# cooling_system.net
KiCad netlist of a schematic drawn in EAGLE
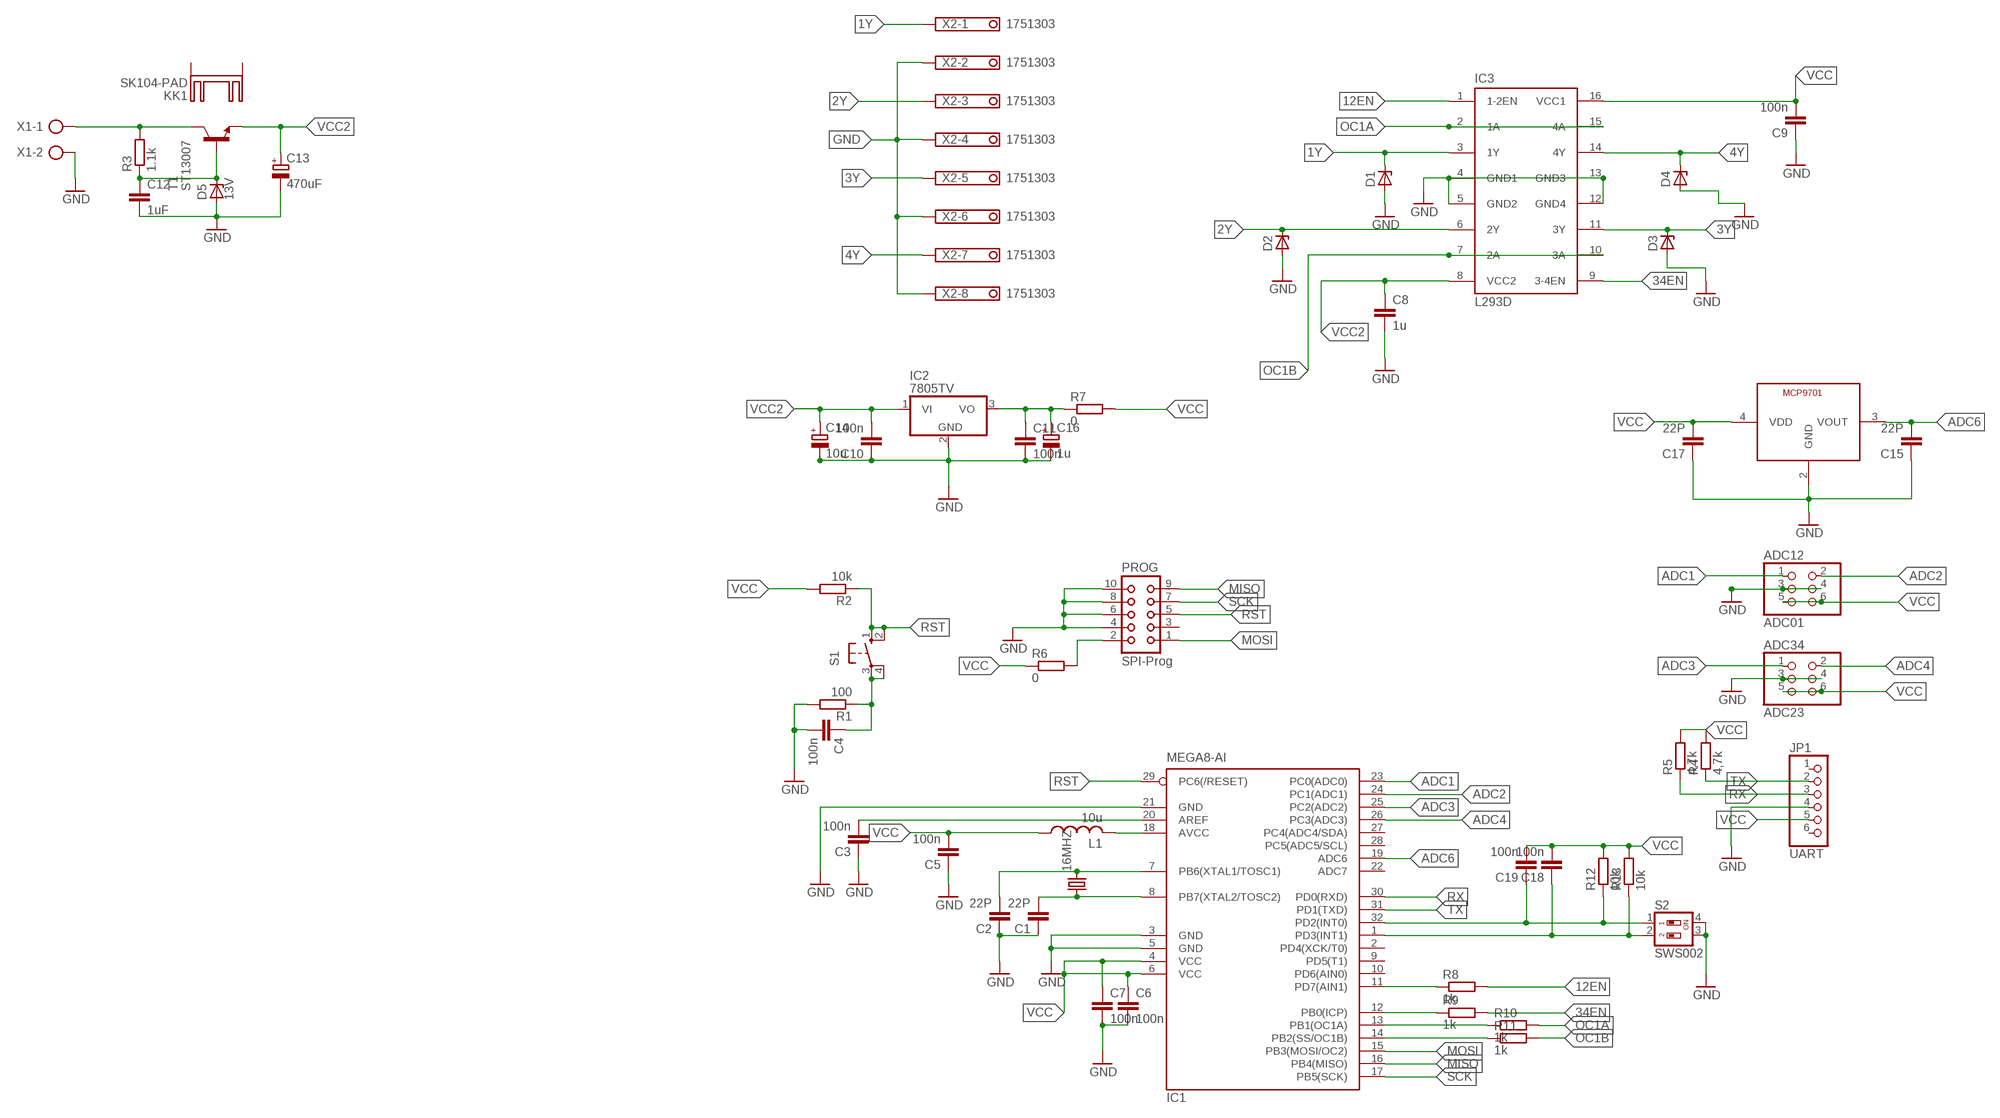
[diagram p0: schematic, sheet 1]

(export (version "E")
  (design (tool "Eeschema 10.0.6"))
  (components
    (comp (ref "16MHZ")
      (value "CRYSTALHC18U-V")
      (footprint "eagle-import:HC18U-V")
      (libsource (lib "eagle-import") (part "CRYSTALHC18U-V"))
    )
    (comp (ref "ADC12")
      (value "ADC01")
      (footprint "eagle-import:2X03")
      (libsource (lib "eagle-import") (part "PINHD-2X3"))
    )
    (comp (ref "ADC34")
      (value "ADC23")
      (footprint "eagle-import:2X03")
      (libsource (lib "eagle-import") (part "PINHD-2X3"))
    )
    (comp (ref "C1")
      (value "22P")
      (footprint "eagle-import:C0805K")
      (libsource (lib "eagle-import") (part "C-EUC0805K"))
    )
    (comp (ref "C2")
      (value "22P")
      (footprint "eagle-import:C0805K")
      (libsource (lib "eagle-import") (part "C-EUC0805K"))
    )
    (comp (ref "C3")
      (value "100n")
      (footprint "eagle-import:C0805K")
      (libsource (lib "eagle-import") (part "C-EUC0805K"))
    )
    (comp (ref "C4")
      (value "100n")
      (footprint "eagle-import:C0805K")
      (libsource (lib "eagle-import") (part "C-EUC0805K"))
    )
    (comp (ref "C5")
      (value "100n")
      (footprint "eagle-import:C0805K")
      (libsource (lib "eagle-import") (part "C-EUC0805K"))
    )
    (comp (ref "C6")
      (value "100n")
      (footprint "eagle-import:C0805K")
      (libsource (lib "eagle-import") (part "C-EUC0805K"))
    )
    (comp (ref "C7")
      (value "100n")
      (footprint "eagle-import:C0805K")
      (libsource (lib "eagle-import") (part "C-EUC0805K"))
    )
    (comp (ref "C8")
      (value "1u")
      (footprint "eagle-import:C0805K")
      (libsource (lib "eagle-import") (part "C-EUC0805K"))
    )
    (comp (ref "C9")
      (value "100n")
      (footprint "eagle-import:C0805K")
      (libsource (lib "eagle-import") (part "C-EUC0805K"))
    )
    (comp (ref "C10")
      (value "100n")
      (footprint "eagle-import:C0805K")
      (libsource (lib "eagle-import") (part "C-EUC0805K"))
    )
    (comp (ref "C11")
      (value "100n")
      (footprint "eagle-import:C0805K")
      (libsource (lib "eagle-import") (part "C-EUC0805K"))
    )
    (comp (ref "C12")
      (value "1uF")
      (footprint "eagle-import:C0805K")
      (libsource (lib "eagle-import") (part "C-EUC0805K"))
    )
    (comp (ref "C13")
      (value "470uF")
      (footprint "eagle-import:E5-10,5")
      (libsource (lib "eagle-import") (part "CPOL-EUE5-10.5"))
    )
    (comp (ref "C14")
      (value "10u")
      (footprint "eagle-import:153CLV-0505")
      (libsource (lib "eagle-import") (part "CPOL-EU153CLV-0505"))
    )
    (comp (ref "C15")
      (value "22P")
      (footprint "eagle-import:C0805K")
      (libsource (lib "eagle-import") (part "C-EUC0805K"))
    )
    (comp (ref "C16")
      (value "1u")
      (footprint "eagle-import:153CLV-0405")
      (libsource (lib "eagle-import") (part "CPOL-EU153CLV-0405"))
    )
    (comp (ref "C17")
      (value "22P")
      (footprint "eagle-import:C0805K")
      (libsource (lib "eagle-import") (part "C-EUC0805K"))
    )
    (comp (ref "C18")
      (value "100n")
      (footprint "eagle-import:C0805K")
      (libsource (lib "eagle-import") (part "C-EUC0805K"))
    )
    (comp (ref "C19")
      (value "100n")
      (footprint "eagle-import:C0805K")
      (libsource (lib "eagle-import") (part "C-EUC0805K"))
    )
    (comp (ref "D1")
      (value "ZENER-DIODEDO35Z10")
      (footprint "eagle-import:DO35Z10")
      (libsource (lib "eagle-import") (part "ZENER-DIODEDO35Z10"))
    )
    (comp (ref "D2")
      (value "ZENER-DIODEDO35Z10")
      (footprint "eagle-import:DO35Z10")
      (libsource (lib "eagle-import") (part "ZENER-DIODEDO35Z10"))
    )
    (comp (ref "D3")
      (value "ZENER-DIODEDO35Z10")
      (footprint "eagle-import:DO35Z10")
      (libsource (lib "eagle-import") (part "ZENER-DIODEDO35Z10"))
    )
    (comp (ref "D4")
      (value "ZENER-DIODEDO35Z10")
      (footprint "eagle-import:DO35Z10")
      (libsource (lib "eagle-import") (part "ZENER-DIODEDO35Z10"))
    )
    (comp (ref "D5")
      (value "13V")
      (footprint "eagle-import:SOT23")
      (libsource (lib "eagle-import") (part "ZENER-DIODESOT23"))
    )
    (comp (ref "IC1")
      (value "MEGA8-AI")
      (footprint "eagle-import:TQFP32-08")
      (fields (field (name "MPN") "ATMEGA8-16AU"))
      (libsource (lib "eagle-import") (part "MEGA8-AI"))
    )
    (comp (ref "IC2")
      (value "7805TV")
      (footprint "eagle-import:TO220V")
      (libsource (lib "eagle-import") (part "78TV05"))
    )
    (comp (ref "IC3")
      (value "L293D")
      (footprint "eagle-import:DIL16")
      (libsource (lib "eagle-import") (part "L293D"))
    )
    (comp (ref "JP1")
      (value "UART")
      (footprint "eagle-import:1X06")
      (libsource (lib "eagle-import") (part "PINHD-1X6"))
    )
    (comp (ref "KK1")
      (value "SK104-PAD")
      (footprint "eagle-import:SK104-PAD")
      (libsource (lib "eagle-import") (part "SK104-PAD"))
    )
    (comp (ref "L1")
      (value "10u")
      (footprint "eagle-import:0207_10")
      (libsource (lib "eagle-import") (part "L-US0207/10"))
    )
    (comp (ref "PROG")
      (value "SPI-Prog")
      (footprint "eagle-import:CON10")
      (libsource (lib "eagle-import") (part "CON10"))
    )
    (comp (ref "R1")
      (value "100")
      (footprint "eagle-import:0207_10")
      (libsource (lib "eagle-import") (part "R-EU_0207/10"))
    )
    (comp (ref "R2")
      (value "10k")
      (footprint "eagle-import:0207_10")
      (libsource (lib "eagle-import") (part "R-EU_0207/10"))
    )
    (comp (ref "R3")
      (value "1.1k")
      (footprint "eagle-import:R0805")
      (libsource (lib "eagle-import") (part "R-EU_R0805"))
    )
    (comp (ref "R4")
      (value "4,7k")
      (footprint "eagle-import:R0805")
      (libsource (lib "eagle-import") (part "R-EU_R0805"))
    )
    (comp (ref "R5")
      (value "4,7k")
      (footprint "eagle-import:R0805")
      (libsource (lib "eagle-import") (part "R-EU_R0805"))
    )
    (comp (ref "R6")
      (value "0")
      (footprint "eagle-import:R0805")
      (libsource (lib "eagle-import") (part "R-EU_R0805"))
    )
    (comp (ref "R7")
      (value "0")
      (footprint "eagle-import:R0805")
      (libsource (lib "eagle-import") (part "R-EU_R0805"))
    )
    (comp (ref "R8")
      (value "1k")
      (footprint "eagle-import:R0805")
      (libsource (lib "eagle-import") (part "R-EU_R0805"))
    )
    (comp (ref "R9")
      (value "1k")
      (footprint "eagle-import:R0805")
      (libsource (lib "eagle-import") (part "R-EU_R0805"))
    )
    (comp (ref "R10")
      (value "1k")
      (footprint "eagle-import:R0805")
      (libsource (lib "eagle-import") (part "R-EU_R0805"))
    )
    (comp (ref "R11")
      (value "1k")
      (footprint "eagle-import:R0805")
      (libsource (lib "eagle-import") (part "R-EU_R0805"))
    )
    (comp (ref "R12")
      (value "10k")
      (footprint "eagle-import:R0805")
      (libsource (lib "eagle-import") (part "R-EU_R0805"))
    )
    (comp (ref "R13")
      (value "10k")
      (footprint "eagle-import:R0805")
      (libsource (lib "eagle-import") (part "R-EU_R0805"))
    )
    (comp (ref "S1")
      (value "10-XX")
      (footprint "eagle-import:B3F-10XX")
      (fields (field (name "MPN") "B3F-1000"))
      (libsource (lib "eagle-import") (part "10-XX"))
    )
    (comp (ref "S2")
      (value "SWS002")
      (footprint "eagle-import:SMS-002")
      (libsource (lib "eagle-import") (part "SWS002"))
    )
    (comp (ref "T1")
      (value "ST13007")
      (footprint "eagle-import:TO220AV")
      (libsource (lib "eagle-import") (part "2SC2509V"))
    )
    (comp (ref "U$2")
      (value "MCP9701")
      (footprint "eagle-import:SC70-5L")
      (libsource (lib "eagle-import") (part "MCP9701"))
    )
    (comp (ref "X1")
      (value "AK300/2")
      (footprint "eagle-import:AK300_2")
      (libsource (lib "eagle-import") (part "AK300/2"))
    )
    (comp (ref "X2")
      (value "1751303")
      (footprint "eagle-import:1751303")
      (libsource (lib "eagle-import") (part "1751303"))
    )
  )
  (nets
    (net (code "1") (name "1Y") (class "Default")
      (node (ref "D1") (pin "C") (pinfunction "C_C") (pintype "passive"))
      (node (ref "IC3") (pin "3") (pinfunction "1Y_3") (pintype "output"))
      (node (ref "X2") (pin "1") (pinfunction "K_1") (pintype "passive"))
    )
    (net (code "2") (name "2Y") (class "Default")
      (node (ref "D2") (pin "C") (pinfunction "C_C") (pintype "passive"))
      (node (ref "IC3") (pin "6") (pinfunction "2Y_6") (pintype "output"))
      (node (ref "X2") (pin "3") (pinfunction "K_3") (pintype "passive"))
    )
    (net (code "3") (name "3Y") (class "Default")
      (node (ref "D3") (pin "C") (pinfunction "C_C") (pintype "passive"))
      (node (ref "IC3") (pin "11") (pinfunction "3Y_11") (pintype "output"))
      (node (ref "X2") (pin "5") (pinfunction "K_5") (pintype "passive"))
    )
    (net (code "4") (name "4Y") (class "Default")
      (node (ref "D4") (pin "C") (pinfunction "C_C") (pintype "passive"))
      (node (ref "IC3") (pin "14") (pinfunction "4Y_14") (pintype "output"))
      (node (ref "X2") (pin "7") (pinfunction "K_7") (pintype "passive"))
    )
    (net (code "5") (name "12EN") (class "Default")
      (node (ref "IC3") (pin "1") (pinfunction "1-2EN_1") (pintype "input"))
      (node (ref "R8") (pin "2") (pinfunction "2_2") (pintype "passive"))
    )
    (net (code "6") (name "34EN") (class "Default")
      (node (ref "IC3") (pin "9") (pinfunction "3-4EN_9") (pintype "input"))
      (node (ref "R9") (pin "2") (pinfunction "2_2") (pintype "passive"))
    )
    (net (code "7") (name "ADC1") (class "Default")
      (node (ref "ADC12") (pin "1") (pinfunction "1_1") (pintype "passive"))
      (node (ref "IC1") (pin "23") (pinfunction "PC0(ADC0)_23") (pintype "bidirectional"))
    )
    (net (code "8") (name "ADC2") (class "Default")
      (node (ref "ADC12") (pin "2") (pinfunction "2_2") (pintype "passive"))
      (node (ref "IC1") (pin "24") (pinfunction "PC1(ADC1)_24") (pintype "bidirectional"))
    )
    (net (code "9") (name "ADC3") (class "Default")
      (node (ref "ADC34") (pin "1") (pinfunction "1_1") (pintype "passive"))
      (node (ref "IC1") (pin "25") (pinfunction "PC2(ADC2)_25") (pintype "bidirectional"))
    )
    (net (code "10") (name "ADC4") (class "Default")
      (node (ref "ADC34") (pin "2") (pinfunction "2_2") (pintype "passive"))
      (node (ref "IC1") (pin "26") (pinfunction "PC3(ADC3)_26") (pintype "bidirectional"))
    )
    (net (code "11") (name "ADC6") (class "Default")
      (node (ref "C15") (pin "2") (pinfunction "2_2") (pintype "passive"))
      (node (ref "IC1") (pin "19") (pinfunction "ADC6_19") (pintype "bidirectional"))
      (node (ref "U$2") (pin "3") (pinfunction "VOUT_3") (pintype "bidirectional"))
    )
    (net (code "12") (name "GND") (class "Default")
      (node (ref "ADC12") (pin "3") (pinfunction "3_3") (pintype "passive"))
      (node (ref "ADC12") (pin "4") (pinfunction "4_4") (pintype "passive"))
      (node (ref "ADC34") (pin "3") (pinfunction "3_3") (pintype "passive"))
      (node (ref "ADC34") (pin "4") (pinfunction "4_4") (pintype "passive"))
      (node (ref "C1") (pin "1") (pinfunction "1_1") (pintype "passive"))
      (node (ref "C10") (pin "1") (pinfunction "1_1") (pintype "passive"))
      (node (ref "C11") (pin "2") (pinfunction "2_2") (pintype "passive"))
      (node (ref "C12") (pin "2") (pinfunction "2_2") (pintype "passive"))
      (node (ref "C13") (pin "-") (pinfunction "-_-") (pintype "passive"))
      (node (ref "C14") (pin "-") (pinfunction "-_-") (pintype "passive"))
      (node (ref "C15") (pin "1") (pinfunction "1_1") (pintype "passive"))
      (node (ref "C16") (pin "-") (pinfunction "-_-") (pintype "passive"))
      (node (ref "C17") (pin "1") (pinfunction "1_1") (pintype "passive"))
      (node (ref "C2") (pin "1") (pinfunction "1_1") (pintype "passive"))
      (node (ref "C3") (pin "1") (pinfunction "1_1") (pintype "passive"))
      (node (ref "C4") (pin "2") (pinfunction "2_2") (pintype "passive"))
      (node (ref "C5") (pin "1") (pinfunction "1_1") (pintype "passive"))
      (node (ref "C6") (pin "2") (pinfunction "2_2") (pintype "passive"))
      (node (ref "C7") (pin "2") (pinfunction "2_2") (pintype "passive"))
      (node (ref "C8") (pin "2") (pinfunction "2_2") (pintype "passive"))
      (node (ref "C9") (pin "1") (pinfunction "1_1") (pintype "passive"))
      (node (ref "D1") (pin "A") (pinfunction "A_A") (pintype "passive"))
      (node (ref "D2") (pin "A") (pinfunction "A_A") (pintype "passive"))
      (node (ref "D3") (pin "A") (pinfunction "A_A") (pintype "passive"))
      (node (ref "D4") (pin "A") (pinfunction "A_A") (pintype "passive"))
      (node (ref "D5") (pin "1") (pinfunction "A_1") (pintype "passive"))
      (node (ref "IC1") (pin "21") (pinfunction "GND_21") (pintype "power_in"))
      (node (ref "IC1") (pin "3") (pinfunction "GND_3") (pintype "power_in"))
      (node (ref "IC1") (pin "5") (pinfunction "GND_5") (pintype "power_in"))
      (node (ref "IC2") (pin "2") (pinfunction "GND_2") (pintype "passive"))
      (node (ref "IC3") (pin "12") (pinfunction "GND4_12") (pintype "power_in"))
      (node (ref "IC3") (pin "13") (pinfunction "GND3_13") (pintype "power_in"))
      (node (ref "IC3") (pin "4") (pinfunction "GND1_4") (pintype "power_in"))
      (node (ref "IC3") (pin "5") (pinfunction "GND2_5") (pintype "power_in"))
      (node (ref "JP1") (pin "4") (pinfunction "4_4") (pintype "passive"))
      (node (ref "PROG") (pin "10") (pinfunction "10_10") (pintype "passive"))
      (node (ref "PROG") (pin "4") (pinfunction "4_4") (pintype "passive"))
      (node (ref "PROG") (pin "6") (pinfunction "6_6") (pintype "passive"))
      (node (ref "PROG") (pin "8") (pinfunction "8_8") (pintype "passive"))
      (node (ref "R1") (pin "2") (pinfunction "2_2") (pintype "passive"))
      (node (ref "S2") (pin "3") (pinfunction "3_3") (pintype "passive"))
      (node (ref "S2") (pin "4") (pinfunction "4_4") (pintype "passive"))
      (node (ref "U$2") (pin "2") (pinfunction "GND_2") (pintype "bidirectional"))
      (node (ref "X1") (pin "2") (pinfunction "KL_2") (pintype "passive"))
      (node (ref "X2") (pin "2") (pinfunction "K_2") (pintype "passive"))
      (node (ref "X2") (pin "4") (pinfunction "K_4") (pintype "passive"))
      (node (ref "X2") (pin "6") (pinfunction "K_6") (pintype "passive"))
      (node (ref "X2") (pin "8") (pinfunction "K_8") (pintype "passive"))
    )
    (net (code "13") (name "MISO") (class "Default")
      (node (ref "IC1") (pin "16") (pinfunction "PB4(MISO)_16") (pintype "bidirectional"))
      (node (ref "PROG") (pin "9") (pinfunction "9_9") (pintype "passive"))
    )
    (net (code "14") (name "MOSI") (class "Default")
      (node (ref "IC1") (pin "15") (pinfunction "PB3(MOSI/OC2)_15") (pintype "bidirectional"))
      (node (ref "PROG") (pin "1") (pinfunction "1_1") (pintype "passive"))
    )
    (net (code "15") (name "Net-(D5-C)") (class "Default")
      (node (ref "C12") (pin "1") (pinfunction "1_1") (pintype "passive"))
      (node (ref "D5") (pin "3") (pinfunction "C_3") (pintype "passive"))
      (node (ref "R3") (pin "1") (pinfunction "1_1") (pintype "passive"))
      (node (ref "T1") (pin "1") (pinfunction "B_1") (pintype "passive"))
    )
    (net (code "16") (name "Net-(IC1-AREF)") (class "Default")
      (node (ref "C3") (pin "2") (pinfunction "2_2") (pintype "passive"))
      (node (ref "IC1") (pin "20") (pinfunction "AREF_20") (pintype "passive"))
    )
    (net (code "17") (name "Net-(IC1-AVCC)") (class "Default")
      (node (ref "IC1") (pin "18") (pinfunction "AVCC_18") (pintype "power_in"))
      (node (ref "L1") (pin "2") (pinfunction "2_2") (pintype "passive"))
    )
    (net (code "18") (name "Net-(IC1-PB0(ICP))") (class "Default")
      (node (ref "IC1") (pin "12") (pinfunction "PB0(ICP)_12") (pintype "bidirectional"))
      (node (ref "R9") (pin "1") (pinfunction "1_1") (pintype "passive"))
    )
    (net (code "19") (name "Net-(IC1-PB1(OC1A))") (class "Default")
      (node (ref "IC1") (pin "13") (pinfunction "PB1(OC1A)_13") (pintype "bidirectional"))
      (node (ref "R10") (pin "1") (pinfunction "1_1") (pintype "passive"))
    )
    (net (code "20") (name "Net-(IC1-PB2(SS{slash}OC1B))") (class "Default")
      (node (ref "IC1") (pin "14") (pinfunction "PB2(SS/OC1B)_14") (pintype "bidirectional"))
      (node (ref "R11") (pin "1") (pinfunction "1_1") (pintype "passive"))
    )
    (net (code "21") (name "Net-(IC1-PB6(XTAL1{slash}TOSC1))") (class "Default")
      (node (ref "16MHZ") (pin "2") (pinfunction "2_2") (pintype "passive"))
      (node (ref "C2") (pin "2") (pinfunction "2_2") (pintype "passive"))
      (node (ref "IC1") (pin "7") (pinfunction "PB6(XTAL1/TOSC1)_7") (pintype "bidirectional"))
    )
    (net (code "22") (name "Net-(IC1-PB7(XTAL2{slash}TOSC2))") (class "Default")
      (node (ref "16MHZ") (pin "1") (pinfunction "1_1") (pintype "passive"))
      (node (ref "C1") (pin "2") (pinfunction "2_2") (pintype "passive"))
      (node (ref "IC1") (pin "8") (pinfunction "PB7(XTAL2/TOSC2)_8") (pintype "bidirectional"))
    )
    (net (code "23") (name "Net-(IC1-PD2(INT0))") (class "Default")
      (node (ref "C19") (pin "1") (pinfunction "1_1") (pintype "passive"))
      (node (ref "IC1") (pin "32") (pinfunction "PD2(INT0)_32") (pintype "bidirectional"))
      (node (ref "R12") (pin "1") (pinfunction "1_1") (pintype "passive"))
      (node (ref "S2") (pin "1") (pinfunction "1_1") (pintype "passive"))
    )
    (net (code "24") (name "Net-(IC1-PD3(INT1))") (class "Default")
      (node (ref "C18") (pin "1") (pinfunction "1_1") (pintype "passive"))
      (node (ref "IC1") (pin "1") (pinfunction "PD3(INT1)_1") (pintype "bidirectional"))
      (node (ref "R13") (pin "1") (pinfunction "1_1") (pintype "passive"))
      (node (ref "S2") (pin "2") (pinfunction "2_2") (pintype "passive"))
    )
    (net (code "25") (name "Net-(IC1-PD7(AIN1))") (class "Default")
      (node (ref "IC1") (pin "11") (pinfunction "PD7(AIN1)_11") (pintype "bidirectional"))
      (node (ref "R8") (pin "1") (pinfunction "1_1") (pintype "passive"))
    )
    (net (code "26") (name "Net-(IC2-VO)") (class "Default")
      (node (ref "C11") (pin "1") (pinfunction "1_1") (pintype "passive"))
      (node (ref "C16") (pin "+") (pinfunction "+_+") (pintype "passive"))
      (node (ref "IC2") (pin "3") (pinfunction "VO_3") (pintype "passive"))
      (node (ref "R7") (pin "1") (pinfunction "1_1") (pintype "passive"))
    )
    (net (code "27") (name "Net-(PROG-Pad2)") (class "Default")
      (node (ref "PROG") (pin "2") (pinfunction "2_2") (pintype "passive"))
      (node (ref "R6") (pin "2") (pinfunction "2_2") (pintype "passive"))
    )
    (net (code "28") (name "Net-(S1-P)") (class "Default")
      (node (ref "C4") (pin "1") (pinfunction "1_1") (pintype "passive"))
      (node (ref "R1") (pin "1") (pinfunction "1_1") (pintype "passive"))
      (node (ref "S1") (pin "3") (pinfunction "P_3") (pintype "passive"))
      (node (ref "S1") (pin "4") (pinfunction "P1_4") (pintype "passive"))
    )
    (net (code "29") (name "Net-(T1-C)") (class "Default")
      (node (ref "R3") (pin "2") (pinfunction "2_2") (pintype "passive"))
      (node (ref "T1") (pin "2") (pinfunction "C_2") (pintype "passive"))
      (node (ref "X1") (pin "1") (pinfunction "KL_1") (pintype "passive"))
    )
    (net (code "30") (name "OC1A") (class "Default")
      (node (ref "IC3") (pin "15") (pinfunction "4A_15") (pintype "input"))
      (node (ref "IC3") (pin "2") (pinfunction "1A_2") (pintype "input"))
      (node (ref "R10") (pin "2") (pinfunction "2_2") (pintype "passive"))
    )
    (net (code "31") (name "OC1B") (class "Default")
      (node (ref "IC3") (pin "10") (pinfunction "3A_10") (pintype "input"))
      (node (ref "IC3") (pin "7") (pinfunction "2A_7") (pintype "input"))
      (node (ref "R11") (pin "2") (pinfunction "2_2") (pintype "passive"))
    )
    (net (code "32") (name "RST") (class "Default")
      (node (ref "IC1") (pin "29") (pinfunction "PC6(/RESET)_29") (pintype "bidirectional"))
      (node (ref "PROG") (pin "5") (pinfunction "5_5") (pintype "passive"))
      (node (ref "R2") (pin "1") (pinfunction "1_1") (pintype "passive"))
      (node (ref "S1") (pin "1") (pinfunction "S_1") (pintype "passive"))
      (node (ref "S1") (pin "2") (pinfunction "S1_2") (pintype "passive"))
    )
    (net (code "33") (name "RX") (class "Default")
      (node (ref "IC1") (pin "30") (pinfunction "PD0(RXD)_30") (pintype "bidirectional"))
      (node (ref "JP1") (pin "3") (pinfunction "3_3") (pintype "passive"))
      (node (ref "R5") (pin "1") (pinfunction "1_1") (pintype "passive"))
    )
    (net (code "34") (name "SCK") (class "Default")
      (node (ref "IC1") (pin "17") (pinfunction "PB5(SCK)_17") (pintype "bidirectional"))
      (node (ref "PROG") (pin "7") (pinfunction "7_7") (pintype "passive"))
    )
    (net (code "35") (name "TX") (class "Default")
      (node (ref "IC1") (pin "31") (pinfunction "PD1(TXD)_31") (pintype "bidirectional"))
      (node (ref "JP1") (pin "2") (pinfunction "2_2") (pintype "passive"))
      (node (ref "R4") (pin "1") (pinfunction "1_1") (pintype "passive"))
    )
    (net (code "36") (name "VCC") (class "Default")
      (node (ref "ADC12") (pin "5") (pinfunction "5_5") (pintype "passive"))
      (node (ref "ADC12") (pin "6") (pinfunction "6_6") (pintype "passive"))
      (node (ref "ADC34") (pin "5") (pinfunction "5_5") (pintype "passive"))
      (node (ref "ADC34") (pin "6") (pinfunction "6_6") (pintype "passive"))
      (node (ref "C17") (pin "2") (pinfunction "2_2") (pintype "passive"))
      (node (ref "C18") (pin "2") (pinfunction "2_2") (pintype "passive"))
      (node (ref "C19") (pin "2") (pinfunction "2_2") (pintype "passive"))
      (node (ref "C5") (pin "2") (pinfunction "2_2") (pintype "passive"))
      (node (ref "C6") (pin "1") (pinfunction "1_1") (pintype "passive"))
      (node (ref "C7") (pin "1") (pinfunction "1_1") (pintype "passive"))
      (node (ref "C9") (pin "2") (pinfunction "2_2") (pintype "passive"))
      (node (ref "IC1") (pin "4") (pinfunction "VCC_4") (pintype "power_in"))
      (node (ref "IC1") (pin "6") (pinfunction "VCC_6") (pintype "power_in"))
      (node (ref "IC3") (pin "16") (pinfunction "VCC1_16") (pintype "power_in"))
      (node (ref "JP1") (pin "5") (pinfunction "5_5") (pintype "passive"))
      (node (ref "L1") (pin "1") (pinfunction "1_1") (pintype "passive"))
      (node (ref "R12") (pin "2") (pinfunction "2_2") (pintype "passive"))
      (node (ref "R13") (pin "2") (pinfunction "2_2") (pintype "passive"))
      (node (ref "R2") (pin "2") (pinfunction "2_2") (pintype "passive"))
      (node (ref "R4") (pin "2") (pinfunction "2_2") (pintype "passive"))
      (node (ref "R5") (pin "2") (pinfunction "2_2") (pintype "passive"))
      (node (ref "R6") (pin "1") (pinfunction "1_1") (pintype "passive"))
      (node (ref "R7") (pin "2") (pinfunction "2_2") (pintype "passive"))
      (node (ref "U$2") (pin "4") (pinfunction "VDD_4") (pintype "bidirectional"))
    )
    (net (code "37") (name "VCC2") (class "Default")
      (node (ref "C10") (pin "2") (pinfunction "2_2") (pintype "passive"))
      (node (ref "C13") (pin "+") (pinfunction "+_+") (pintype "passive"))
      (node (ref "C14") (pin "+") (pinfunction "+_+") (pintype "passive"))
      (node (ref "C8") (pin "1") (pinfunction "1_1") (pintype "passive"))
      (node (ref "IC2") (pin "1") (pinfunction "VI_1") (pintype "input"))
      (node (ref "IC3") (pin "8") (pinfunction "VCC2_8") (pintype "power_in"))
      (node (ref "T1") (pin "3") (pinfunction "E_3") (pintype "passive"))
    )
    (net (code "38") (name "unconnected-(IC1-ADC7-Pad22)") (class "Default")
      (node (ref "IC1") (pin "22") (pinfunction "ADC7_22") (pintype "bidirectional"))
    )
    (net (code "39") (name "unconnected-(IC1-PC4(ADC4{slash}SDA)-Pad27)") (class "Default")
      (node (ref "IC1") (pin "27") (pinfunction "PC4(ADC4/SDA)_27") (pintype "bidirectional"))
    )
    (net (code "40") (name "unconnected-(IC1-PC5(ADC5{slash}SCL)-Pad28)") (class "Default")
      (node (ref "IC1") (pin "28") (pinfunction "PC5(ADC5/SCL)_28") (pintype "bidirectional"))
    )
    (net (code "41") (name "unconnected-(IC1-PD4(XCK{slash}T0)-Pad2)") (class "Default")
      (node (ref "IC1") (pin "2") (pinfunction "PD4(XCK/T0)_2") (pintype "bidirectional"))
    )
    (net (code "42") (name "unconnected-(IC1-PD5(T1)-Pad9)") (class "Default")
      (node (ref "IC1") (pin "9") (pinfunction "PD5(T1)_9") (pintype "bidirectional"))
    )
    (net (code "43") (name "unconnected-(IC1-PD6(AIN0)-Pad10)") (class "Default")
      (node (ref "IC1") (pin "10") (pinfunction "PD6(AIN0)_10") (pintype "bidirectional"))
    )
    (net (code "44") (name "unconnected-(JP1-Pad1)") (class "Default")
      (node (ref "JP1") (pin "1") (pinfunction "1_1") (pintype "passive"))
    )
    (net (code "45") (name "unconnected-(JP1-Pad6)") (class "Default")
      (node (ref "JP1") (pin "6") (pinfunction "6_6") (pintype "passive"))
    )
    (net (code "46") (name "unconnected-(KK1-K-PadK1)") (class "Default")
      (node (ref "KK1") (pin "K1") (pinfunction "K_K1") (pintype "passive"))
    )
    (net (code "47") (name "unconnected-(KK1-K-PadK2)") (class "Default")
      (node (ref "KK1") (pin "K2") (pinfunction "K_K2") (pintype "passive"))
    )
    (net (code "48") (name "unconnected-(PROG-Pad3)") (class "Default")
      (node (ref "PROG") (pin "3") (pinfunction "3_3") (pintype "passive"))
    )
  )
)
